# hoop_v2.net
KiCad netlist of a schematic drawn in EAGLE
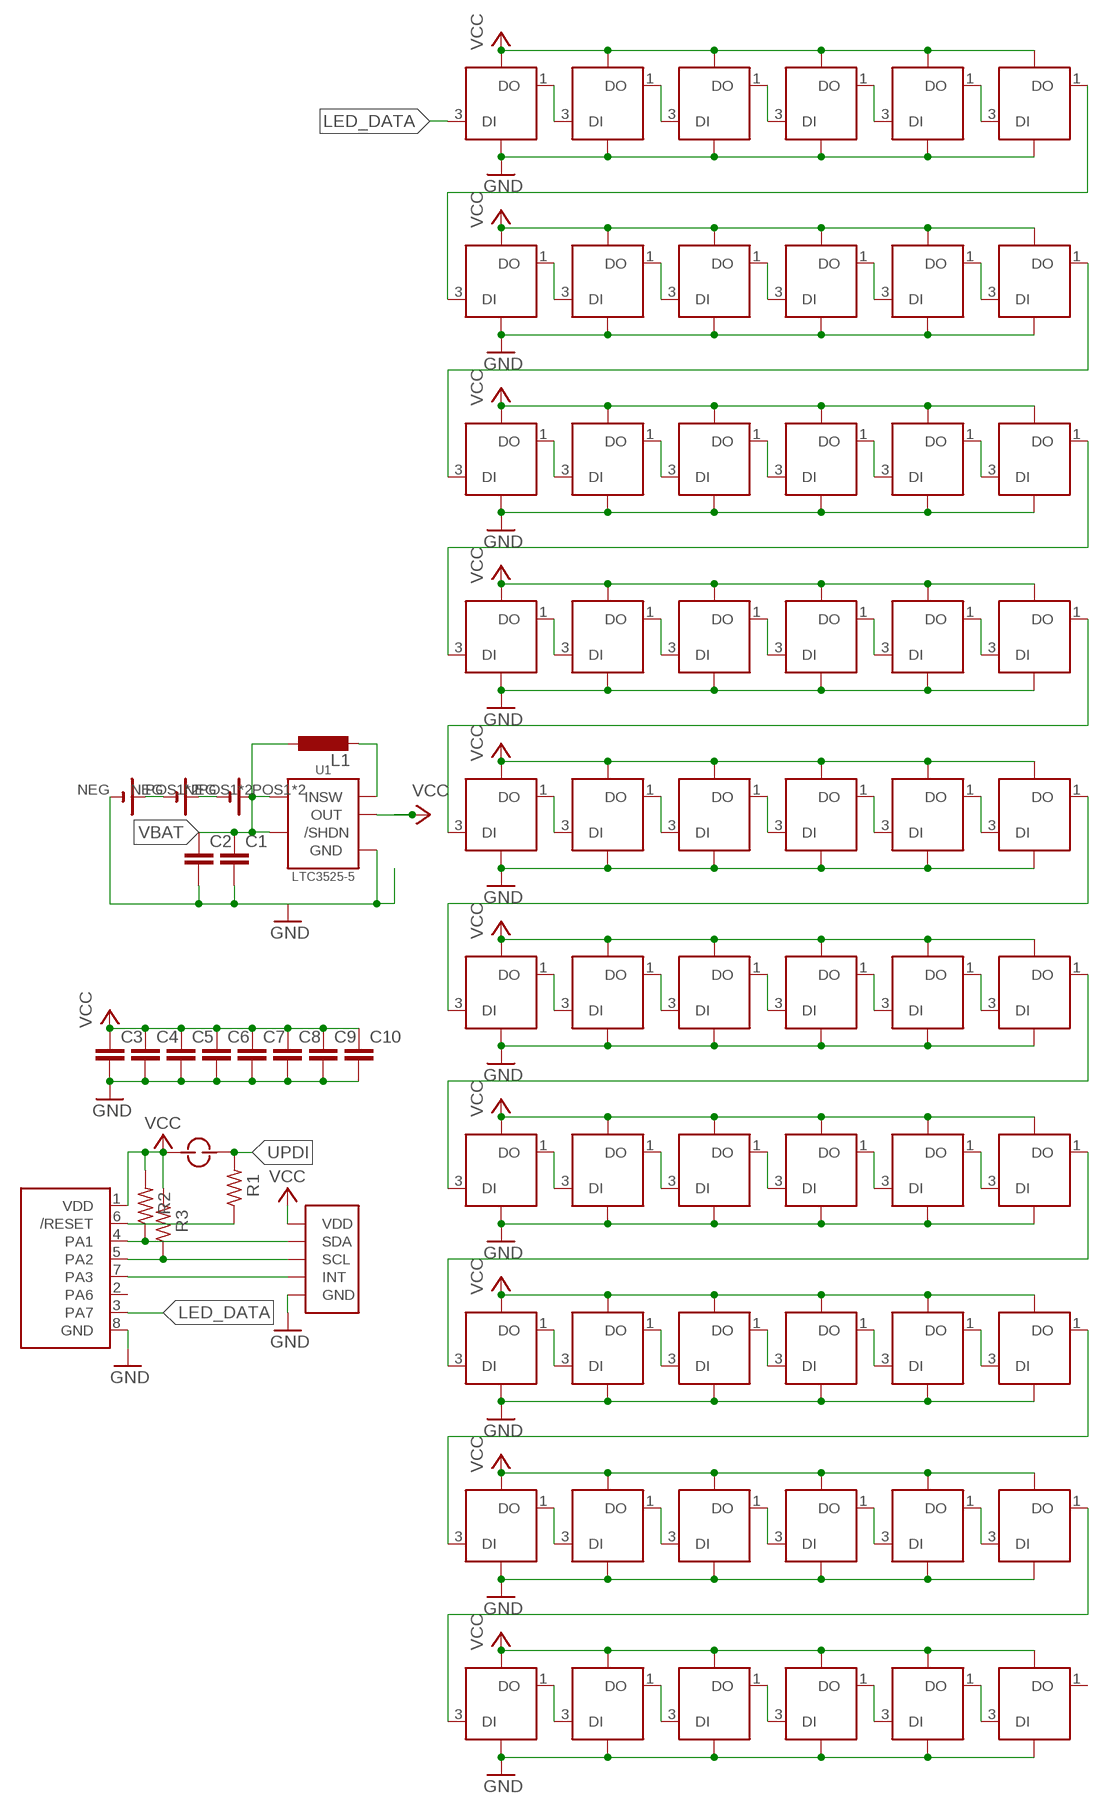
[diagram p0: schematic, sheet 1]

(export (version "E")
  (design (tool "Eeschema 10.0.6"))
  (components
    (comp (ref "B1")
      (value "P312")
      (footprint "eagle-import:P312_CLIP")
      (libsource (lib "eagle-import") (part "P312"))
    )
    (comp (ref "B2")
      (value "P312")
      (footprint "eagle-import:P312_CLIP")
      (libsource (lib "eagle-import") (part "P312"))
    )
    (comp (ref "B3")
      (value "P312")
      (footprint "eagle-import:P312_CLIP")
      (libsource (lib "eagle-import") (part "P312"))
    )
    (comp (ref "C1")
      (value "C-EUC0805")
      (footprint "eagle-import:C0805")
      (libsource (lib "eagle-import") (part "C-EUC0805"))
    )
    (comp (ref "C2")
      (value "C-EUC0805")
      (footprint "eagle-import:C0805")
      (libsource (lib "eagle-import") (part "C-EUC0805"))
    )
    (comp (ref "C3")
      (value "C-EUC0805")
      (footprint "eagle-import:C0805")
      (libsource (lib "eagle-import") (part "C-EUC0805"))
    )
    (comp (ref "C4")
      (value "C-EUC0805")
      (footprint "eagle-import:C0805")
      (libsource (lib "eagle-import") (part "C-EUC0805"))
    )
    (comp (ref "C5")
      (value "C-EUC0805")
      (footprint "eagle-import:C0805")
      (libsource (lib "eagle-import") (part "C-EUC0805"))
    )
    (comp (ref "C6")
      (value "C-EUC0805")
      (footprint "eagle-import:C0805")
      (libsource (lib "eagle-import") (part "C-EUC0805"))
    )
    (comp (ref "C7")
      (value "C-EUC0805")
      (footprint "eagle-import:C0805")
      (libsource (lib "eagle-import") (part "C-EUC0805"))
    )
    (comp (ref "C8")
      (value "C-EUC0805")
      (footprint "eagle-import:C0805")
      (libsource (lib "eagle-import") (part "C-EUC0805"))
    )
    (comp (ref "C9")
      (value "C-EUC0805")
      (footprint "eagle-import:C0805")
      (libsource (lib "eagle-import") (part "C-EUC0805"))
    )
    (comp (ref "C10")
      (value "C-EUC0805")
      (footprint "eagle-import:C0805")
      (libsource (lib "eagle-import") (part "C-EUC0805"))
    )
    (comp (ref "D1")
      (value "SMD-LX0707RGB-TR")
      (footprint "eagle-import:SMD-LX0707RGB-TR")
      (libsource (lib "eagle-import") (part "SMD-LX0707RGB-TR"))
    )
    (comp (ref "D2")
      (value "SMD-LX0707RGB-TR")
      (footprint "eagle-import:SMD-LX0707RGB-TR")
      (libsource (lib "eagle-import") (part "SMD-LX0707RGB-TR"))
    )
    (comp (ref "D3")
      (value "SMD-LX0707RGB-TR")
      (footprint "eagle-import:SMD-LX0707RGB-TR")
      (libsource (lib "eagle-import") (part "SMD-LX0707RGB-TR"))
    )
    (comp (ref "D4")
      (value "SMD-LX0707RGB-TR")
      (footprint "eagle-import:SMD-LX0707RGB-TR")
      (libsource (lib "eagle-import") (part "SMD-LX0707RGB-TR"))
    )
    (comp (ref "D5")
      (value "SMD-LX0707RGB-TR")
      (footprint "eagle-import:SMD-LX0707RGB-TR")
      (libsource (lib "eagle-import") (part "SMD-LX0707RGB-TR"))
    )
    (comp (ref "D6")
      (value "SMD-LX0707RGB-TR")
      (footprint "eagle-import:SMD-LX0707RGB-TR")
      (libsource (lib "eagle-import") (part "SMD-LX0707RGB-TR"))
    )
    (comp (ref "D7")
      (value "SMD-LX0707RGB-TR")
      (footprint "eagle-import:SMD-LX0707RGB-TR")
      (libsource (lib "eagle-import") (part "SMD-LX0707RGB-TR"))
    )
    (comp (ref "D8")
      (value "SMD-LX0707RGB-TR")
      (footprint "eagle-import:SMD-LX0707RGB-TR")
      (libsource (lib "eagle-import") (part "SMD-LX0707RGB-TR"))
    )
    (comp (ref "D9")
      (value "SMD-LX0707RGB-TR")
      (footprint "eagle-import:SMD-LX0707RGB-TR")
      (libsource (lib "eagle-import") (part "SMD-LX0707RGB-TR"))
    )
    (comp (ref "D10")
      (value "SMD-LX0707RGB-TR")
      (footprint "eagle-import:SMD-LX0707RGB-TR")
      (libsource (lib "eagle-import") (part "SMD-LX0707RGB-TR"))
    )
    (comp (ref "D11")
      (value "SMD-LX0707RGB-TR")
      (footprint "eagle-import:SMD-LX0707RGB-TR")
      (libsource (lib "eagle-import") (part "SMD-LX0707RGB-TR"))
    )
    (comp (ref "D12")
      (value "SMD-LX0707RGB-TR")
      (footprint "eagle-import:SMD-LX0707RGB-TR")
      (libsource (lib "eagle-import") (part "SMD-LX0707RGB-TR"))
    )
    (comp (ref "D13")
      (value "SMD-LX0707RGB-TR")
      (footprint "eagle-import:SMD-LX0707RGB-TR")
      (libsource (lib "eagle-import") (part "SMD-LX0707RGB-TR"))
    )
    (comp (ref "D14")
      (value "SMD-LX0707RGB-TR")
      (footprint "eagle-import:SMD-LX0707RGB-TR")
      (libsource (lib "eagle-import") (part "SMD-LX0707RGB-TR"))
    )
    (comp (ref "D15")
      (value "SMD-LX0707RGB-TR")
      (footprint "eagle-import:SMD-LX0707RGB-TR")
      (libsource (lib "eagle-import") (part "SMD-LX0707RGB-TR"))
    )
    (comp (ref "D16")
      (value "SMD-LX0707RGB-TR")
      (footprint "eagle-import:SMD-LX0707RGB-TR")
      (libsource (lib "eagle-import") (part "SMD-LX0707RGB-TR"))
    )
    (comp (ref "D17")
      (value "SMD-LX0707RGB-TR")
      (footprint "eagle-import:SMD-LX0707RGB-TR")
      (libsource (lib "eagle-import") (part "SMD-LX0707RGB-TR"))
    )
    (comp (ref "D18")
      (value "SMD-LX0707RGB-TR")
      (footprint "eagle-import:SMD-LX0707RGB-TR")
      (libsource (lib "eagle-import") (part "SMD-LX0707RGB-TR"))
    )
    (comp (ref "D19")
      (value "SMD-LX0707RGB-TR")
      (footprint "eagle-import:SMD-LX0707RGB-TR")
      (libsource (lib "eagle-import") (part "SMD-LX0707RGB-TR"))
    )
    (comp (ref "D20")
      (value "SMD-LX0707RGB-TR")
      (footprint "eagle-import:SMD-LX0707RGB-TR")
      (libsource (lib "eagle-import") (part "SMD-LX0707RGB-TR"))
    )
    (comp (ref "D21")
      (value "SMD-LX0707RGB-TR")
      (footprint "eagle-import:SMD-LX0707RGB-TR")
      (libsource (lib "eagle-import") (part "SMD-LX0707RGB-TR"))
    )
    (comp (ref "D22")
      (value "SMD-LX0707RGB-TR")
      (footprint "eagle-import:SMD-LX0707RGB-TR")
      (libsource (lib "eagle-import") (part "SMD-LX0707RGB-TR"))
    )
    (comp (ref "D23")
      (value "SMD-LX0707RGB-TR")
      (footprint "eagle-import:SMD-LX0707RGB-TR")
      (libsource (lib "eagle-import") (part "SMD-LX0707RGB-TR"))
    )
    (comp (ref "D24")
      (value "SMD-LX0707RGB-TR")
      (footprint "eagle-import:SMD-LX0707RGB-TR")
      (libsource (lib "eagle-import") (part "SMD-LX0707RGB-TR"))
    )
    (comp (ref "D25")
      (value "SMD-LX0707RGB-TR")
      (footprint "eagle-import:SMD-LX0707RGB-TR")
      (libsource (lib "eagle-import") (part "SMD-LX0707RGB-TR"))
    )
    (comp (ref "D26")
      (value "SMD-LX0707RGB-TR")
      (footprint "eagle-import:SMD-LX0707RGB-TR")
      (libsource (lib "eagle-import") (part "SMD-LX0707RGB-TR"))
    )
    (comp (ref "D27")
      (value "SMD-LX0707RGB-TR")
      (footprint "eagle-import:SMD-LX0707RGB-TR")
      (libsource (lib "eagle-import") (part "SMD-LX0707RGB-TR"))
    )
    (comp (ref "D28")
      (value "SMD-LX0707RGB-TR")
      (footprint "eagle-import:SMD-LX0707RGB-TR")
      (libsource (lib "eagle-import") (part "SMD-LX0707RGB-TR"))
    )
    (comp (ref "D29")
      (value "SMD-LX0707RGB-TR")
      (footprint "eagle-import:SMD-LX0707RGB-TR")
      (libsource (lib "eagle-import") (part "SMD-LX0707RGB-TR"))
    )
    (comp (ref "D30")
      (value "SMD-LX0707RGB-TR")
      (footprint "eagle-import:SMD-LX0707RGB-TR")
      (libsource (lib "eagle-import") (part "SMD-LX0707RGB-TR"))
    )
    (comp (ref "D31")
      (value "SMD-LX0707RGB-TR")
      (footprint "eagle-import:SMD-LX0707RGB-TR")
      (libsource (lib "eagle-import") (part "SMD-LX0707RGB-TR"))
    )
    (comp (ref "D32")
      (value "SMD-LX0707RGB-TR")
      (footprint "eagle-import:SMD-LX0707RGB-TR")
      (libsource (lib "eagle-import") (part "SMD-LX0707RGB-TR"))
    )
    (comp (ref "D33")
      (value "SMD-LX0707RGB-TR")
      (footprint "eagle-import:SMD-LX0707RGB-TR")
      (libsource (lib "eagle-import") (part "SMD-LX0707RGB-TR"))
    )
    (comp (ref "D34")
      (value "SMD-LX0707RGB-TR")
      (footprint "eagle-import:SMD-LX0707RGB-TR")
      (libsource (lib "eagle-import") (part "SMD-LX0707RGB-TR"))
    )
    (comp (ref "D35")
      (value "SMD-LX0707RGB-TR")
      (footprint "eagle-import:SMD-LX0707RGB-TR")
      (libsource (lib "eagle-import") (part "SMD-LX0707RGB-TR"))
    )
    (comp (ref "D36")
      (value "SMD-LX0707RGB-TR")
      (footprint "eagle-import:SMD-LX0707RGB-TR")
      (libsource (lib "eagle-import") (part "SMD-LX0707RGB-TR"))
    )
    (comp (ref "D37")
      (value "SMD-LX0707RGB-TR")
      (footprint "eagle-import:SMD-LX0707RGB-TR")
      (libsource (lib "eagle-import") (part "SMD-LX0707RGB-TR"))
    )
    (comp (ref "D38")
      (value "SMD-LX0707RGB-TR")
      (footprint "eagle-import:SMD-LX0707RGB-TR")
      (libsource (lib "eagle-import") (part "SMD-LX0707RGB-TR"))
    )
    (comp (ref "D39")
      (value "SMD-LX0707RGB-TR")
      (footprint "eagle-import:SMD-LX0707RGB-TR")
      (libsource (lib "eagle-import") (part "SMD-LX0707RGB-TR"))
    )
    (comp (ref "D40")
      (value "SMD-LX0707RGB-TR")
      (footprint "eagle-import:SMD-LX0707RGB-TR")
      (libsource (lib "eagle-import") (part "SMD-LX0707RGB-TR"))
    )
    (comp (ref "D41")
      (value "SMD-LX0707RGB-TR")
      (footprint "eagle-import:SMD-LX0707RGB-TR")
      (libsource (lib "eagle-import") (part "SMD-LX0707RGB-TR"))
    )
    (comp (ref "D42")
      (value "SMD-LX0707RGB-TR")
      (footprint "eagle-import:SMD-LX0707RGB-TR")
      (libsource (lib "eagle-import") (part "SMD-LX0707RGB-TR"))
    )
    (comp (ref "D43")
      (value "SMD-LX0707RGB-TR")
      (footprint "eagle-import:SMD-LX0707RGB-TR")
      (libsource (lib "eagle-import") (part "SMD-LX0707RGB-TR"))
    )
    (comp (ref "D44")
      (value "SMD-LX0707RGB-TR")
      (footprint "eagle-import:SMD-LX0707RGB-TR")
      (libsource (lib "eagle-import") (part "SMD-LX0707RGB-TR"))
    )
    (comp (ref "D45")
      (value "SMD-LX0707RGB-TR")
      (footprint "eagle-import:SMD-LX0707RGB-TR")
      (libsource (lib "eagle-import") (part "SMD-LX0707RGB-TR"))
    )
    (comp (ref "D46")
      (value "SMD-LX0707RGB-TR")
      (footprint "eagle-import:SMD-LX0707RGB-TR")
      (libsource (lib "eagle-import") (part "SMD-LX0707RGB-TR"))
    )
    (comp (ref "D47")
      (value "SMD-LX0707RGB-TR")
      (footprint "eagle-import:SMD-LX0707RGB-TR")
      (libsource (lib "eagle-import") (part "SMD-LX0707RGB-TR"))
    )
    (comp (ref "D48")
      (value "SMD-LX0707RGB-TR")
      (footprint "eagle-import:SMD-LX0707RGB-TR")
      (libsource (lib "eagle-import") (part "SMD-LX0707RGB-TR"))
    )
    (comp (ref "D49")
      (value "SMD-LX0707RGB-TR")
      (footprint "eagle-import:SMD-LX0707RGB-TR")
      (libsource (lib "eagle-import") (part "SMD-LX0707RGB-TR"))
    )
    (comp (ref "D50")
      (value "SMD-LX0707RGB-TR")
      (footprint "eagle-import:SMD-LX0707RGB-TR")
      (libsource (lib "eagle-import") (part "SMD-LX0707RGB-TR"))
    )
    (comp (ref "D51")
      (value "SMD-LX0707RGB-TR")
      (footprint "eagle-import:SMD-LX0707RGB-TR")
      (libsource (lib "eagle-import") (part "SMD-LX0707RGB-TR"))
    )
    (comp (ref "D52")
      (value "SMD-LX0707RGB-TR")
      (footprint "eagle-import:SMD-LX0707RGB-TR")
      (libsource (lib "eagle-import") (part "SMD-LX0707RGB-TR"))
    )
    (comp (ref "D53")
      (value "SMD-LX0707RGB-TR")
      (footprint "eagle-import:SMD-LX0707RGB-TR")
      (libsource (lib "eagle-import") (part "SMD-LX0707RGB-TR"))
    )
    (comp (ref "D54")
      (value "SMD-LX0707RGB-TR")
      (footprint "eagle-import:SMD-LX0707RGB-TR")
      (libsource (lib "eagle-import") (part "SMD-LX0707RGB-TR"))
    )
    (comp (ref "D55")
      (value "SMD-LX0707RGB-TR")
      (footprint "eagle-import:SMD-LX0707RGB-TR")
      (libsource (lib "eagle-import") (part "SMD-LX0707RGB-TR"))
    )
    (comp (ref "D56")
      (value "SMD-LX0707RGB-TR")
      (footprint "eagle-import:SMD-LX0707RGB-TR")
      (libsource (lib "eagle-import") (part "SMD-LX0707RGB-TR"))
    )
    (comp (ref "D57")
      (value "SMD-LX0707RGB-TR")
      (footprint "eagle-import:SMD-LX0707RGB-TR")
      (libsource (lib "eagle-import") (part "SMD-LX0707RGB-TR"))
    )
    (comp (ref "D58")
      (value "SMD-LX0707RGB-TR")
      (footprint "eagle-import:SMD-LX0707RGB-TR")
      (libsource (lib "eagle-import") (part "SMD-LX0707RGB-TR"))
    )
    (comp (ref "D59")
      (value "SMD-LX0707RGB-TR")
      (footprint "eagle-import:SMD-LX0707RGB-TR")
      (libsource (lib "eagle-import") (part "SMD-LX0707RGB-TR"))
    )
    (comp (ref "D60")
      (value "SMD-LX0707RGB-TR")
      (footprint "eagle-import:SMD-LX0707RGB-TR")
      (libsource (lib "eagle-import") (part "SMD-LX0707RGB-TR"))
    )
    (comp (ref "J1")
      (value "JMP")
      (footprint "eagle-import:SOLDER_JMP")
      (libsource (lib "eagle-import") (part "JMP"))
    )
    (comp (ref "L1")
      (value "L-EUL3216C")
      (footprint "eagle-import:L3216C")
      (libsource (lib "eagle-import") (part "L-EUL3216C"))
    )
    (comp (ref "R1")
      (value "R-US_R0805")
      (footprint "eagle-import:R0805")
      (libsource (lib "eagle-import") (part "R-US_R0805"))
    )
    (comp (ref "R2")
      (value "R-US_R0805")
      (footprint "eagle-import:R0805")
      (libsource (lib "eagle-import") (part "R-US_R0805"))
    )
    (comp (ref "R3")
      (value "R-US_R0805")
      (footprint "eagle-import:R0805")
      (libsource (lib "eagle-import") (part "R-US_R0805"))
    )
    (comp (ref "U1")
      (value "LTC3525")
      (footprint "eagle-import:SOP65P210X100-6N")
      (libsource (lib "eagle-import") (part "LTC3525"))
    )
    (comp (ref "U2")
      (value "MXC6255XU")
      (footprint "eagle-import:RESCAV110P300X300X105-6N")
      (libsource (lib "eagle-import") (part "MXC6255XU"))
    )
    (comp (ref "U3")
      (value "ATTINY202")
      (footprint "eagle-import:SOIC127P600X175-8N")
      (libsource (lib "eagle-import") (part "ATTINY202"))
    )
  )
  (nets
    (net (code "1") (name "GND") (class "Default")
      (node (ref "B1") (pin "NEG") (pinfunction "-_NEG") (pintype "passive"))
      (node (ref "C1") (pin "2") (pinfunction "2_2") (pintype "passive"))
      (node (ref "C10") (pin "2") (pinfunction "2_2") (pintype "passive"))
      (node (ref "C2") (pin "2") (pinfunction "2_2") (pintype "passive"))
      (node (ref "C3") (pin "2") (pinfunction "2_2") (pintype "passive"))
      (node (ref "C4") (pin "2") (pinfunction "2_2") (pintype "passive"))
      (node (ref "C5") (pin "2") (pinfunction "2_2") (pintype "passive"))
      (node (ref "C6") (pin "2") (pinfunction "2_2") (pintype "passive"))
      (node (ref "C7") (pin "2") (pinfunction "2_2") (pintype "passive"))
      (node (ref "C8") (pin "2") (pinfunction "2_2") (pintype "passive"))
      (node (ref "C9") (pin "2") (pinfunction "2_2") (pintype "passive"))
      (node (ref "D1") (pin "4") (pinfunction "GND_4") (pintype "bidirectional"))
      (node (ref "D10") (pin "4") (pinfunction "GND_4") (pintype "bidirectional"))
      (node (ref "D11") (pin "4") (pinfunction "GND_4") (pintype "bidirectional"))
      (node (ref "D12") (pin "4") (pinfunction "GND_4") (pintype "bidirectional"))
      (node (ref "D13") (pin "4") (pinfunction "GND_4") (pintype "bidirectional"))
      (node (ref "D14") (pin "4") (pinfunction "GND_4") (pintype "bidirectional"))
      (node (ref "D15") (pin "4") (pinfunction "GND_4") (pintype "bidirectional"))
      (node (ref "D16") (pin "4") (pinfunction "GND_4") (pintype "bidirectional"))
      (node (ref "D17") (pin "4") (pinfunction "GND_4") (pintype "bidirectional"))
      (node (ref "D18") (pin "4") (pinfunction "GND_4") (pintype "bidirectional"))
      (node (ref "D19") (pin "4") (pinfunction "GND_4") (pintype "bidirectional"))
      (node (ref "D2") (pin "4") (pinfunction "GND_4") (pintype "bidirectional"))
      (node (ref "D20") (pin "4") (pinfunction "GND_4") (pintype "bidirectional"))
      (node (ref "D21") (pin "4") (pinfunction "GND_4") (pintype "bidirectional"))
      (node (ref "D22") (pin "4") (pinfunction "GND_4") (pintype "bidirectional"))
      (node (ref "D23") (pin "4") (pinfunction "GND_4") (pintype "bidirectional"))
      (node (ref "D24") (pin "4") (pinfunction "GND_4") (pintype "bidirectional"))
      (node (ref "D25") (pin "4") (pinfunction "GND_4") (pintype "bidirectional"))
      (node (ref "D26") (pin "4") (pinfunction "GND_4") (pintype "bidirectional"))
      (node (ref "D27") (pin "4") (pinfunction "GND_4") (pintype "bidirectional"))
      (node (ref "D28") (pin "4") (pinfunction "GND_4") (pintype "bidirectional"))
      (node (ref "D29") (pin "4") (pinfunction "GND_4") (pintype "bidirectional"))
      (node (ref "D3") (pin "4") (pinfunction "GND_4") (pintype "bidirectional"))
      (node (ref "D30") (pin "4") (pinfunction "GND_4") (pintype "bidirectional"))
      (node (ref "D31") (pin "4") (pinfunction "GND_4") (pintype "bidirectional"))
      (node (ref "D32") (pin "4") (pinfunction "GND_4") (pintype "bidirectional"))
      (node (ref "D33") (pin "4") (pinfunction "GND_4") (pintype "bidirectional"))
      (node (ref "D34") (pin "4") (pinfunction "GND_4") (pintype "bidirectional"))
      (node (ref "D35") (pin "4") (pinfunction "GND_4") (pintype "bidirectional"))
      (node (ref "D36") (pin "4") (pinfunction "GND_4") (pintype "bidirectional"))
      (node (ref "D37") (pin "4") (pinfunction "GND_4") (pintype "bidirectional"))
      (node (ref "D38") (pin "4") (pinfunction "GND_4") (pintype "bidirectional"))
      (node (ref "D39") (pin "4") (pinfunction "GND_4") (pintype "bidirectional"))
      (node (ref "D4") (pin "4") (pinfunction "GND_4") (pintype "bidirectional"))
      (node (ref "D40") (pin "4") (pinfunction "GND_4") (pintype "bidirectional"))
      (node (ref "D41") (pin "4") (pinfunction "GND_4") (pintype "bidirectional"))
      (node (ref "D42") (pin "4") (pinfunction "GND_4") (pintype "bidirectional"))
      (node (ref "D43") (pin "4") (pinfunction "GND_4") (pintype "bidirectional"))
      (node (ref "D44") (pin "4") (pinfunction "GND_4") (pintype "bidirectional"))
      (node (ref "D45") (pin "4") (pinfunction "GND_4") (pintype "bidirectional"))
      (node (ref "D46") (pin "4") (pinfunction "GND_4") (pintype "bidirectional"))
      (node (ref "D47") (pin "4") (pinfunction "GND_4") (pintype "bidirectional"))
      (node (ref "D48") (pin "4") (pinfunction "GND_4") (pintype "bidirectional"))
      (node (ref "D49") (pin "4") (pinfunction "GND_4") (pintype "bidirectional"))
      (node (ref "D5") (pin "4") (pinfunction "GND_4") (pintype "bidirectional"))
      (node (ref "D50") (pin "4") (pinfunction "GND_4") (pintype "bidirectional"))
      (node (ref "D51") (pin "4") (pinfunction "GND_4") (pintype "bidirectional"))
      (node (ref "D52") (pin "4") (pinfunction "GND_4") (pintype "bidirectional"))
      (node (ref "D53") (pin "4") (pinfunction "GND_4") (pintype "bidirectional"))
      (node (ref "D54") (pin "4") (pinfunction "GND_4") (pintype "bidirectional"))
      (node (ref "D55") (pin "4") (pinfunction "GND_4") (pintype "bidirectional"))
      (node (ref "D56") (pin "4") (pinfunction "GND_4") (pintype "bidirectional"))
      (node (ref "D57") (pin "4") (pinfunction "GND_4") (pintype "bidirectional"))
      (node (ref "D58") (pin "4") (pinfunction "GND_4") (pintype "bidirectional"))
      (node (ref "D59") (pin "4") (pinfunction "GND_4") (pintype "bidirectional"))
      (node (ref "D6") (pin "4") (pinfunction "GND_4") (pintype "bidirectional"))
      (node (ref "D60") (pin "4") (pinfunction "GND_4") (pintype "bidirectional"))
      (node (ref "D7") (pin "4") (pinfunction "GND_4") (pintype "bidirectional"))
      (node (ref "D8") (pin "4") (pinfunction "GND_4") (pintype "bidirectional"))
      (node (ref "D9") (pin "4") (pinfunction "GND_4") (pintype "bidirectional"))
      (node (ref "U1") (pin "2") (pinfunction "GND_2") (pintype "bidirectional"))
      (node (ref "U1") (pin "5") (pinfunction "GND_5") (pintype "bidirectional"))
      (node (ref "U2") (pin "6") (pinfunction "GND_6") (pintype "bidirectional"))
      (node (ref "U3") (pin "8") (pinfunction "GND_8") (pintype "bidirectional"))
    )
    (net (code "2") (name "LED_DATA") (class "Default")
      (node (ref "D1") (pin "3") (pinfunction "DI_3") (pintype "bidirectional"))
      (node (ref "U3") (pin "3") (pinfunction "PA7_3") (pintype "bidirectional"))
    )
    (net (code "3") (name "Net-(B2--)") (class "Default")
      (node (ref "B1") (pin "POS1") (pinfunction "+_POS1") (pintype "passive"))
      (node (ref "B1") (pin "POS2") (pinfunction "+_POS2") (pintype "passive"))
      (node (ref "B2") (pin "NEG") (pinfunction "-_NEG") (pintype "passive"))
    )
    (net (code "4") (name "Net-(B3--)") (class "Default")
      (node (ref "B2") (pin "POS1") (pinfunction "+_POS1") (pintype "passive"))
      (node (ref "B2") (pin "POS2") (pinfunction "+_POS2") (pintype "passive"))
      (node (ref "B3") (pin "NEG") (pinfunction "-_NEG") (pintype "passive"))
    )
    (net (code "5") (name "Net-(D1-DO)") (class "Default")
      (node (ref "D1") (pin "1") (pinfunction "DO_1") (pintype "bidirectional"))
      (node (ref "D2") (pin "3") (pinfunction "DI_3") (pintype "bidirectional"))
    )
    (net (code "6") (name "Net-(D2-DO)") (class "Default")
      (node (ref "D2") (pin "1") (pinfunction "DO_1") (pintype "bidirectional"))
      (node (ref "D3") (pin "3") (pinfunction "DI_3") (pintype "bidirectional"))
    )
    (net (code "7") (name "Net-(D3-DO)") (class "Default")
      (node (ref "D3") (pin "1") (pinfunction "DO_1") (pintype "bidirectional"))
      (node (ref "D4") (pin "3") (pinfunction "DI_3") (pintype "bidirectional"))
    )
    (net (code "8") (name "Net-(D4-DO)") (class "Default")
      (node (ref "D4") (pin "1") (pinfunction "DO_1") (pintype "bidirectional"))
      (node (ref "D5") (pin "3") (pinfunction "DI_3") (pintype "bidirectional"))
    )
    (net (code "9") (name "Net-(D5-DO)") (class "Default")
      (node (ref "D5") (pin "1") (pinfunction "DO_1") (pintype "bidirectional"))
      (node (ref "D6") (pin "3") (pinfunction "DI_3") (pintype "bidirectional"))
    )
    (net (code "10") (name "Net-(D6-DO)") (class "Default")
      (node (ref "D6") (pin "1") (pinfunction "DO_1") (pintype "bidirectional"))
      (node (ref "D7") (pin "3") (pinfunction "DI_3") (pintype "bidirectional"))
    )
    (net (code "11") (name "Net-(D7-DO)") (class "Default")
      (node (ref "D7") (pin "1") (pinfunction "DO_1") (pintype "bidirectional"))
      (node (ref "D8") (pin "3") (pinfunction "DI_3") (pintype "bidirectional"))
    )
    (net (code "12") (name "Net-(D8-DO)") (class "Default")
      (node (ref "D8") (pin "1") (pinfunction "DO_1") (pintype "bidirectional"))
      (node (ref "D9") (pin "3") (pinfunction "DI_3") (pintype "bidirectional"))
    )
    (net (code "13") (name "Net-(D10-DI)") (class "Default")
      (node (ref "D10") (pin "3") (pinfunction "DI_3") (pintype "bidirectional"))
      (node (ref "D9") (pin "1") (pinfunction "DO_1") (pintype "bidirectional"))
    )
    (net (code "14") (name "Net-(D10-DO)") (class "Default")
      (node (ref "D10") (pin "1") (pinfunction "DO_1") (pintype "bidirectional"))
      (node (ref "D11") (pin "3") (pinfunction "DI_3") (pintype "bidirectional"))
    )
    (net (code "15") (name "Net-(D11-DO)") (class "Default")
      (node (ref "D11") (pin "1") (pinfunction "DO_1") (pintype "bidirectional"))
      (node (ref "D12") (pin "3") (pinfunction "DI_3") (pintype "bidirectional"))
    )
    (net (code "16") (name "Net-(D12-DO)") (class "Default")
      (node (ref "D12") (pin "1") (pinfunction "DO_1") (pintype "bidirectional"))
      (node (ref "D13") (pin "3") (pinfunction "DI_3") (pintype "bidirectional"))
    )
    (net (code "17") (name "Net-(D13-DO)") (class "Default")
      (node (ref "D13") (pin "1") (pinfunction "DO_1") (pintype "bidirectional"))
      (node (ref "D14") (pin "3") (pinfunction "DI_3") (pintype "bidirectional"))
    )
    (net (code "18") (name "Net-(D14-DO)") (class "Default")
      (node (ref "D14") (pin "1") (pinfunction "DO_1") (pintype "bidirectional"))
      (node (ref "D15") (pin "3") (pinfunction "DI_3") (pintype "bidirectional"))
    )
    (net (code "19") (name "Net-(D15-DO)") (class "Default")
      (node (ref "D15") (pin "1") (pinfunction "DO_1") (pintype "bidirectional"))
      (node (ref "D16") (pin "3") (pinfunction "DI_3") (pintype "bidirectional"))
    )
    (net (code "20") (name "Net-(D16-DO)") (class "Default")
      (node (ref "D16") (pin "1") (pinfunction "DO_1") (pintype "bidirectional"))
      (node (ref "D17") (pin "3") (pinfunction "DI_3") (pintype "bidirectional"))
    )
    (net (code "21") (name "Net-(D17-DO)") (class "Default")
      (node (ref "D17") (pin "1") (pinfunction "DO_1") (pintype "bidirectional"))
      (node (ref "D18") (pin "3") (pinfunction "DI_3") (pintype "bidirectional"))
    )
    (net (code "22") (name "Net-(D18-DO)") (class "Default")
      (node (ref "D18") (pin "1") (pinfunction "DO_1") (pintype "bidirectional"))
      (node (ref "D19") (pin "3") (pinfunction "DI_3") (pintype "bidirectional"))
    )
    (net (code "23") (name "Net-(D19-DO)") (class "Default")
      (node (ref "D19") (pin "1") (pinfunction "DO_1") (pintype "bidirectional"))
      (node (ref "D20") (pin "3") (pinfunction "DI_3") (pintype "bidirectional"))
    )
    (net (code "24") (name "Net-(D20-DO)") (class "Default")
      (node (ref "D20") (pin "1") (pinfunction "DO_1") (pintype "bidirectional"))
      (node (ref "D21") (pin "3") (pinfunction "DI_3") (pintype "bidirectional"))
    )
    (net (code "25") (name "Net-(D21-DO)") (class "Default")
      (node (ref "D21") (pin "1") (pinfunction "DO_1") (pintype "bidirectional"))
      (node (ref "D22") (pin "3") (pinfunction "DI_3") (pintype "bidirectional"))
    )
    (net (code "26") (name "Net-(D22-DO)") (class "Default")
      (node (ref "D22") (pin "1") (pinfunction "DO_1") (pintype "bidirectional"))
      (node (ref "D23") (pin "3") (pinfunction "DI_3") (pintype "bidirectional"))
    )
    (net (code "27") (name "Net-(D23-DO)") (class "Default")
      (node (ref "D23") (pin "1") (pinfunction "DO_1") (pintype "bidirectional"))
      (node (ref "D24") (pin "3") (pinfunction "DI_3") (pintype "bidirectional"))
    )
    (net (code "28") (name "Net-(D24-DO)") (class "Default")
      (node (ref "D24") (pin "1") (pinfunction "DO_1") (pintype "bidirectional"))
      (node (ref "D25") (pin "3") (pinfunction "DI_3") (pintype "bidirectional"))
    )
    (net (code "29") (name "Net-(D25-DO)") (class "Default")
      (node (ref "D25") (pin "1") (pinfunction "DO_1") (pintype "bidirectional"))
      (node (ref "D26") (pin "3") (pinfunction "DI_3") (pintype "bidirectional"))
    )
    (net (code "30") (name "Net-(D26-DO)") (class "Default")
      (node (ref "D26") (pin "1") (pinfunction "DO_1") (pintype "bidirectional"))
      (node (ref "D27") (pin "3") (pinfunction "DI_3") (pintype "bidirectional"))
    )
    (net (code "31") (name "Net-(D27-DO)") (class "Default")
      (node (ref "D27") (pin "1") (pinfunction "DO_1") (pintype "bidirectional"))
      (node (ref "D28") (pin "3") (pinfunction "DI_3") (pintype "bidirectional"))
    )
    (net (code "32") (name "Net-(D28-DO)") (class "Default")
      (node (ref "D28") (pin "1") (pinfunction "DO_1") (pintype "bidirectional"))
      (node (ref "D29") (pin "3") (pinfunction "DI_3") (pintype "bidirectional"))
    )
    (net (code "33") (name "Net-(D29-DO)") (class "Default")
      (node (ref "D29") (pin "1") (pinfunction "DO_1") (pintype "bidirectional"))
      (node (ref "D30") (pin "3") (pinfunction "DI_3") (pintype "bidirectional"))
    )
    (net (code "34") (name "Net-(D30-DO)") (class "Default")
      (node (ref "D30") (pin "1") (pinfunction "DO_1") (pintype "bidirectional"))
      (node (ref "D31") (pin "3") (pinfunction "DI_3") (pintype "bidirectional"))
    )
    (net (code "35") (name "Net-(D31-DO)") (class "Default")
      (node (ref "D31") (pin "1") (pinfunction "DO_1") (pintype "bidirectional"))
      (node (ref "D32") (pin "3") (pinfunction "DI_3") (pintype "bidirectional"))
    )
    (net (code "36") (name "Net-(D32-DO)") (class "Default")
      (node (ref "D32") (pin "1") (pinfunction "DO_1") (pintype "bidirectional"))
      (node (ref "D33") (pin "3") (pinfunction "DI_3") (pintype "bidirectional"))
    )
    (net (code "37") (name "Net-(D33-DO)") (class "Default")
      (node (ref "D33") (pin "1") (pinfunction "DO_1") (pintype "bidirectional"))
      (node (ref "D34") (pin "3") (pinfunction "DI_3") (pintype "bidirectional"))
    )
    (net (code "38") (name "Net-(D34-DO)") (class "Default")
      (node (ref "D34") (pin "1") (pinfunction "DO_1") (pintype "bidirectional"))
      (node (ref "D35") (pin "3") (pinfunction "DI_3") (pintype "bidirectional"))
    )
    (net (code "39") (name "Net-(D35-DO)") (class "Default")
      (node (ref "D35") (pin "1") (pinfunction "DO_1") (pintype "bidirectional"))
      (node (ref "D36") (pin "3") (pinfunction "DI_3") (pintype "bidirectional"))
    )
    (net (code "40") (name "Net-(D36-DO)") (class "Default")
      (node (ref "D36") (pin "1") (pinfunction "DO_1") (pintype "bidirectional"))
      (node (ref "D37") (pin "3") (pinfunction "DI_3") (pintype "bidirectional"))
    )
    (net (code "41") (name "Net-(D37-DO)") (class "Default")
      (node (ref "D37") (pin "1") (pinfunction "DO_1") (pintype "bidirectional"))
      (node (ref "D38") (pin "3") (pinfunction "DI_3") (pintype "bidirectional"))
    )
    (net (code "42") (name "Net-(D38-DO)") (class "Default")
      (node (ref "D38") (pin "1") (pinfunction "DO_1") (pintype "bidirectional"))
      (node (ref "D39") (pin "3") (pinfunction "DI_3") (pintype "bidirectional"))
    )
    (net (code "43") (name "Net-(D39-DO)") (class "Default")
      (node (ref "D39") (pin "1") (pinfunction "DO_1") (pintype "bidirectional"))
      (node (ref "D40") (pin "3") (pinfunction "DI_3") (pintype "bidirectional"))
    )
    (net (code "44") (name "Net-(D40-DO)") (class "Default")
      (node (ref "D40") (pin "1") (pinfunction "DO_1") (pintype "bidirectional"))
      (node (ref "D41") (pin "3") (pinfunction "DI_3") (pintype "bidirectional"))
    )
    (net (code "45") (name "Net-(D41-DO)") (class "Default")
      (node (ref "D41") (pin "1") (pinfunction "DO_1") (pintype "bidirectional"))
      (node (ref "D42") (pin "3") (pinfunction "DI_3") (pintype "bidirectional"))
    )
    (net (code "46") (name "Net-(D42-DO)") (class "Default")
      (node (ref "D42") (pin "1") (pinfunction "DO_1") (pintype "bidirectional"))
      (node (ref "D43") (pin "3") (pinfunction "DI_3") (pintype "bidirectional"))
    )
    (net (code "47") (name "Net-(D43-DO)") (class "Default")
      (node (ref "D43") (pin "1") (pinfunction "DO_1") (pintype "bidirectional"))
      (node (ref "D44") (pin "3") (pinfunction "DI_3") (pintype "bidirectional"))
    )
    (net (code "48") (name "Net-(D44-DO)") (class "Default")
      (node (ref "D44") (pin "1") (pinfunction "DO_1") (pintype "bidirectional"))
      (node (ref "D45") (pin "3") (pinfunction "DI_3") (pintype "bidirectional"))
    )
    (net (code "49") (name "Net-(D45-DO)") (class "Default")
      (node (ref "D45") (pin "1") (pinfunction "DO_1") (pintype "bidirectional"))
      (node (ref "D46") (pin "3") (pinfunction "DI_3") (pintype "bidirectional"))
    )
    (net (code "50") (name "Net-(D46-DO)") (class "Default")
      (node (ref "D46") (pin "1") (pinfunction "DO_1") (pintype "bidirectional"))
      (node (ref "D47") (pin "3") (pinfunction "DI_3") (pintype "bidirectional"))
    )
    (net (code "51") (name "Net-(D47-DO)") (class "Default")
      (node (ref "D47") (pin "1") (pinfunction "DO_1") (pintype "bidirectional"))
      (node (ref "D48") (pin "3") (pinfunction "DI_3") (pintype "bidirectional"))
    )
    (net (code "52") (name "Net-(D48-DO)") (class "Default")
      (node (ref "D48") (pin "1") (pinfunction "DO_1") (pintype "bidirectional"))
      (node (ref "D49") (pin "3") (pinfunction "DI_3") (pintype "bidirectional"))
    )
    (net (code "53") (name "Net-(D49-DO)") (class "Default")
      (node (ref "D49") (pin "1") (pinfunction "DO_1") (pintype "bidirectional"))
      (node (ref "D50") (pin "3") (pinfunction "DI_3") (pintype "bidirectional"))
    )
    (net (code "54") (name "Net-(D50-DO)") (class "Default")
      (node (ref "D50") (pin "1") (pinfunction "DO_1") (pintype "bidirectional"))
      (node (ref "D51") (pin "3") (pinfunction "DI_3") (pintype "bidirectional"))
    )
    (net (code "55") (name "Net-(D51-DO)") (class "Default")
      (node (ref "D51") (pin "1") (pinfunction "DO_1") (pintype "bidirectional"))
      (node (ref "D52") (pin "3") (pinfunction "DI_3") (pintype "bidirectional"))
    )
    (net (code "56") (name "Net-(D52-DO)") (class "Default")
      (node (ref "D52") (pin "1") (pinfunction "DO_1") (pintype "bidirectional"))
      (node (ref "D53") (pin "3") (pinfunction "DI_3") (pintype "bidirectional"))
    )
    (net (code "57") (name "Net-(D53-DO)") (class "Default")
      (node (ref "D53") (pin "1") (pinfunction "DO_1") (pintype "bidirectional"))
      (node (ref "D54") (pin "3") (pinfunction "DI_3") (pintype "bidirectional"))
    )
    (net (code "58") (name "Net-(D54-DO)") (class "Default")
      (node (ref "D54") (pin "1") (pinfunction "DO_1") (pintype "bidirectional"))
      (node (ref "D55") (pin "3") (pinfunction "DI_3") (pintype "bidirectional"))
    )
    (net (code "59") (name "Net-(D55-DO)") (class "Default")
      (node (ref "D55") (pin "1") (pinfunction "DO_1") (pintype "bidirectional"))
      (node (ref "D56") (pin "3") (pinfunction "DI_3") (pintype "bidirectional"))
    )
    (net (code "60") (name "Net-(D56-DO)") (class "Default")
      (node (ref "D56") (pin "1") (pinfunction "DO_1") (pintype "bidirectional"))
      (node (ref "D57") (pin "3") (pinfunction "DI_3") (pintype "bidirectional"))
    )
    (net (code "61") (name "Net-(D57-DO)") (class "Default")
      (node (ref "D57") (pin "1") (pinfunction "DO_1") (pintype "bidirectional"))
      (node (ref "D58") (pin "3") (pinfunction "DI_3") (pintype "bidirectional"))
    )
    (net (code "62") (name "Net-(D58-DO)") (class "Default")
      (node (ref "D58") (pin "1") (pinfunction "DO_1") (pintype "bidirectional"))
      (node (ref "D59") (pin "3") (pinfunction "DI_3") (pintype "bidirectional"))
    )
    (net (code "63") (name "Net-(D59-DO)") (class "Default")
      (node (ref "D59") (pin "1") (pinfunction "DO_1") (pintype "bidirectional"))
      (node (ref "D60") (pin "3") (pinfunction "DI_3") (pintype "bidirectional"))
    )
    (net (code "64") (name "Net-(U1-SW)") (class "Default")
      (node (ref "L1") (pin "2") (pinfunction "2_2") (pintype "passive"))
      (node (ref "U1") (pin "6") (pinfunction "SW_6") (pintype "bidirectional"))
    )
    (net (code "65") (name "Net-(U2-INT)") (class "Default")
      (node (ref "U2") (pin "1") (pinfunction "INT_1") (pintype "bidirectional"))
      (node (ref "U3") (pin "7") (pinfunction "PA3_7") (pintype "bidirectional"))
    )
    (net (code "66") (name "Net-(U2-SCL)") (class "Default")
      (node (ref "R3") (pin "1") (pinfunction "1_1") (pintype "passive"))
      (node (ref "U2") (pin "4") (pinfunction "SCL_4") (pintype "bidirectional"))
      (node (ref "U3") (pin "5") (pinfunction "PA2_5") (pintype "bidirectional"))
    )
    (net (code "67") (name "Net-(U2-SDA)") (class "Default")
      (node (ref "R2") (pin "1") (pinfunction "1_1") (pintype "passive"))
      (node (ref "U2") (pin "5") (pinfunction "SDA_5") (pintype "bidirectional"))
      (node (ref "U3") (pin "4") (pinfunction "PA1_4") (pintype "bidirectional"))
    )
    (net (code "68") (name "Net-(U3-{slash}RESET)") (class "Default")
      (node (ref "R1") (pin "1") (pinfunction "1_1") (pintype "passive"))
      (node (ref "U3") (pin "6") (pinfunction "/RESET_6") (pintype "bidirectional"))
    )
    (net (code "69") (name "UPDI") (class "Default")
      (node (ref "J1") (pin "P$2") (pinfunction "P$2_P$2") (pintype "bidirectional"))
      (node (ref "R1") (pin "2") (pinfunction "2_2") (pintype "passive"))
    )
    (net (code "70") (name "VBAT") (class "Default")
      (node (ref "B3") (pin "POS1") (pinfunction "+_POS1") (pintype "passive"))
      (node (ref "B3") (pin "POS2") (pinfunction "+_POS2") (pintype "passive"))
      (node (ref "C1") (pin "1") (pinfunction "1_1") (pintype "passive"))
      (node (ref "C2") (pin "1") (pinfunction "1_1") (pintype "passive"))
      (node (ref "L1") (pin "1") (pinfunction "1_1") (pintype "passive"))
      (node (ref "U1") (pin "1") (pinfunction "/SHDN_1") (pintype "bidirectional"))
      (node (ref "U1") (pin "3") (pinfunction "IN_3") (pintype "bidirectional"))
    )
    (net (code "71") (name "VCC") (class "Default")
      (node (ref "C10") (pin "1") (pinfunction "1_1") (pintype "passive"))
      (node (ref "C3") (pin "1") (pinfunction "1_1") (pintype "passive"))
      (node (ref "C4") (pin "1") (pinfunction "1_1") (pintype "passive"))
      (node (ref "C5") (pin "1") (pinfunction "1_1") (pintype "passive"))
      (node (ref "C6") (pin "1") (pinfunction "1_1") (pintype "passive"))
      (node (ref "C7") (pin "1") (pinfunction "1_1") (pintype "passive"))
      (node (ref "C8") (pin "1") (pinfunction "1_1") (pintype "passive"))
      (node (ref "C9") (pin "1") (pinfunction "1_1") (pintype "passive"))
      (node (ref "D1") (pin "2") (pinfunction "VDD_2") (pintype "bidirectional"))
      (node (ref "D10") (pin "2") (pinfunction "VDD_2") (pintype "bidirectional"))
      (node (ref "D11") (pin "2") (pinfunction "VDD_2") (pintype "bidirectional"))
      (node (ref "D12") (pin "2") (pinfunction "VDD_2") (pintype "bidirectional"))
      (node (ref "D13") (pin "2") (pinfunction "VDD_2") (pintype "bidirectional"))
      (node (ref "D14") (pin "2") (pinfunction "VDD_2") (pintype "bidirectional"))
      (node (ref "D15") (pin "2") (pinfunction "VDD_2") (pintype "bidirectional"))
      (node (ref "D16") (pin "2") (pinfunction "VDD_2") (pintype "bidirectional"))
      (node (ref "D17") (pin "2") (pinfunction "VDD_2") (pintype "bidirectional"))
      (node (ref "D18") (pin "2") (pinfunction "VDD_2") (pintype "bidirectional"))
      (node (ref "D19") (pin "2") (pinfunction "VDD_2") (pintype "bidirectional"))
      (node (ref "D2") (pin "2") (pinfunction "VDD_2") (pintype "bidirectional"))
      (node (ref "D20") (pin "2") (pinfunction "VDD_2") (pintype "bidirectional"))
      (node (ref "D21") (pin "2") (pinfunction "VDD_2") (pintype "bidirectional"))
      (node (ref "D22") (pin "2") (pinfunction "VDD_2") (pintype "bidirectional"))
      (node (ref "D23") (pin "2") (pinfunction "VDD_2") (pintype "bidirectional"))
      (node (ref "D24") (pin "2") (pinfunction "VDD_2") (pintype "bidirectional"))
      (node (ref "D25") (pin "2") (pinfunction "VDD_2") (pintype "bidirectional"))
      (node (ref "D26") (pin "2") (pinfunction "VDD_2") (pintype "bidirectional"))
      (node (ref "D27") (pin "2") (pinfunction "VDD_2") (pintype "bidirectional"))
      (node (ref "D28") (pin "2") (pinfunction "VDD_2") (pintype "bidirectional"))
      (node (ref "D29") (pin "2") (pinfunction "VDD_2") (pintype "bidirectional"))
      (node (ref "D3") (pin "2") (pinfunction "VDD_2") (pintype "bidirectional"))
      (node (ref "D30") (pin "2") (pinfunction "VDD_2") (pintype "bidirectional"))
      (node (ref "D31") (pin "2") (pinfunction "VDD_2") (pintype "bidirectional"))
      (node (ref "D32") (pin "2") (pinfunction "VDD_2") (pintype "bidirectional"))
      (node (ref "D33") (pin "2") (pinfunction "VDD_2") (pintype "bidirectional"))
      (node (ref "D34") (pin "2") (pinfunction "VDD_2") (pintype "bidirectional"))
      (node (ref "D35") (pin "2") (pinfunction "VDD_2") (pintype "bidirectional"))
      (node (ref "D36") (pin "2") (pinfunction "VDD_2") (pintype "bidirectional"))
      (node (ref "D37") (pin "2") (pinfunction "VDD_2") (pintype "bidirectional"))
      (node (ref "D38") (pin "2") (pinfunction "VDD_2") (pintype "bidirectional"))
      (node (ref "D39") (pin "2") (pinfunction "VDD_2") (pintype "bidirectional"))
      (node (ref "D4") (pin "2") (pinfunction "VDD_2") (pintype "bidirectional"))
      (node (ref "D40") (pin "2") (pinfunction "VDD_2") (pintype "bidirectional"))
      (node (ref "D41") (pin "2") (pinfunction "VDD_2") (pintype "bidirectional"))
      (node (ref "D42") (pin "2") (pinfunction "VDD_2") (pintype "bidirectional"))
      (node (ref "D43") (pin "2") (pinfunction "VDD_2") (pintype "bidirectional"))
      (node (ref "D44") (pin "2") (pinfunction "VDD_2") (pintype "bidirectional"))
      (node (ref "D45") (pin "2") (pinfunction "VDD_2") (pintype "bidirectional"))
      (node (ref "D46") (pin "2") (pinfunction "VDD_2") (pintype "bidirectional"))
      (node (ref "D47") (pin "2") (pinfunction "VDD_2") (pintype "bidirectional"))
      (node (ref "D48") (pin "2") (pinfunction "VDD_2") (pintype "bidirectional"))
      (node (ref "D49") (pin "2") (pinfunction "VDD_2") (pintype "bidirectional"))
      (node (ref "D5") (pin "2") (pinfunction "VDD_2") (pintype "bidirectional"))
      (node (ref "D50") (pin "2") (pinfunction "VDD_2") (pintype "bidirectional"))
      (node (ref "D51") (pin "2") (pinfunction "VDD_2") (pintype "bidirectional"))
      (node (ref "D52") (pin "2") (pinfunction "VDD_2") (pintype "bidirectional"))
      (node (ref "D53") (pin "2") (pinfunction "VDD_2") (pintype "bidirectional"))
      (node (ref "D54") (pin "2") (pinfunction "VDD_2") (pintype "bidirectional"))
      (node (ref "D55") (pin "2") (pinfunction "VDD_2") (pintype "bidirectional"))
      (node (ref "D56") (pin "2") (pinfunction "VDD_2") (pintype "bidirectional"))
      (node (ref "D57") (pin "2") (pinfunction "VDD_2") (pintype "bidirectional"))
      (node (ref "D58") (pin "2") (pinfunction "VDD_2") (pintype "bidirectional"))
      (node (ref "D59") (pin "2") (pinfunction "VDD_2") (pintype "bidirectional"))
      (node (ref "D6") (pin "2") (pinfunction "VDD_2") (pintype "bidirectional"))
      (node (ref "D60") (pin "2") (pinfunction "VDD_2") (pintype "bidirectional"))
      (node (ref "D7") (pin "2") (pinfunction "VDD_2") (pintype "bidirectional"))
      (node (ref "D8") (pin "2") (pinfunction "VDD_2") (pintype "bidirectional"))
      (node (ref "D9") (pin "2") (pinfunction "VDD_2") (pintype "bidirectional"))
      (node (ref "J1") (pin "P$1") (pinfunction "P$1_P$1") (pintype "bidirectional"))
      (node (ref "R2") (pin "2") (pinfunction "2_2") (pintype "passive"))
      (node (ref "R3") (pin "2") (pinfunction "2_2") (pintype "passive"))
      (node (ref "U1") (pin "4") (pinfunction "OUT_4") (pintype "bidirectional"))
      (node (ref "U2") (pin "3") (pinfunction "VDD_3") (pintype "bidirectional"))
      (node (ref "U3") (pin "1") (pinfunction "VDD_1") (pintype "bidirectional"))
    )
    (net (code "72") (name "unconnected-(D60-DO-Pad1)") (class "Default")
      (node (ref "D60") (pin "1") (pinfunction "DO_1") (pintype "bidirectional"))
    )
    (net (code "73") (name "unconnected-(U3-PA6-Pad2)") (class "Default")
      (node (ref "U3") (pin "2") (pinfunction "PA6_2") (pintype "bidirectional"))
    )
  )
)
